# TeensyROM.net
KiCad netlist of a schematic drawn in EAGLE
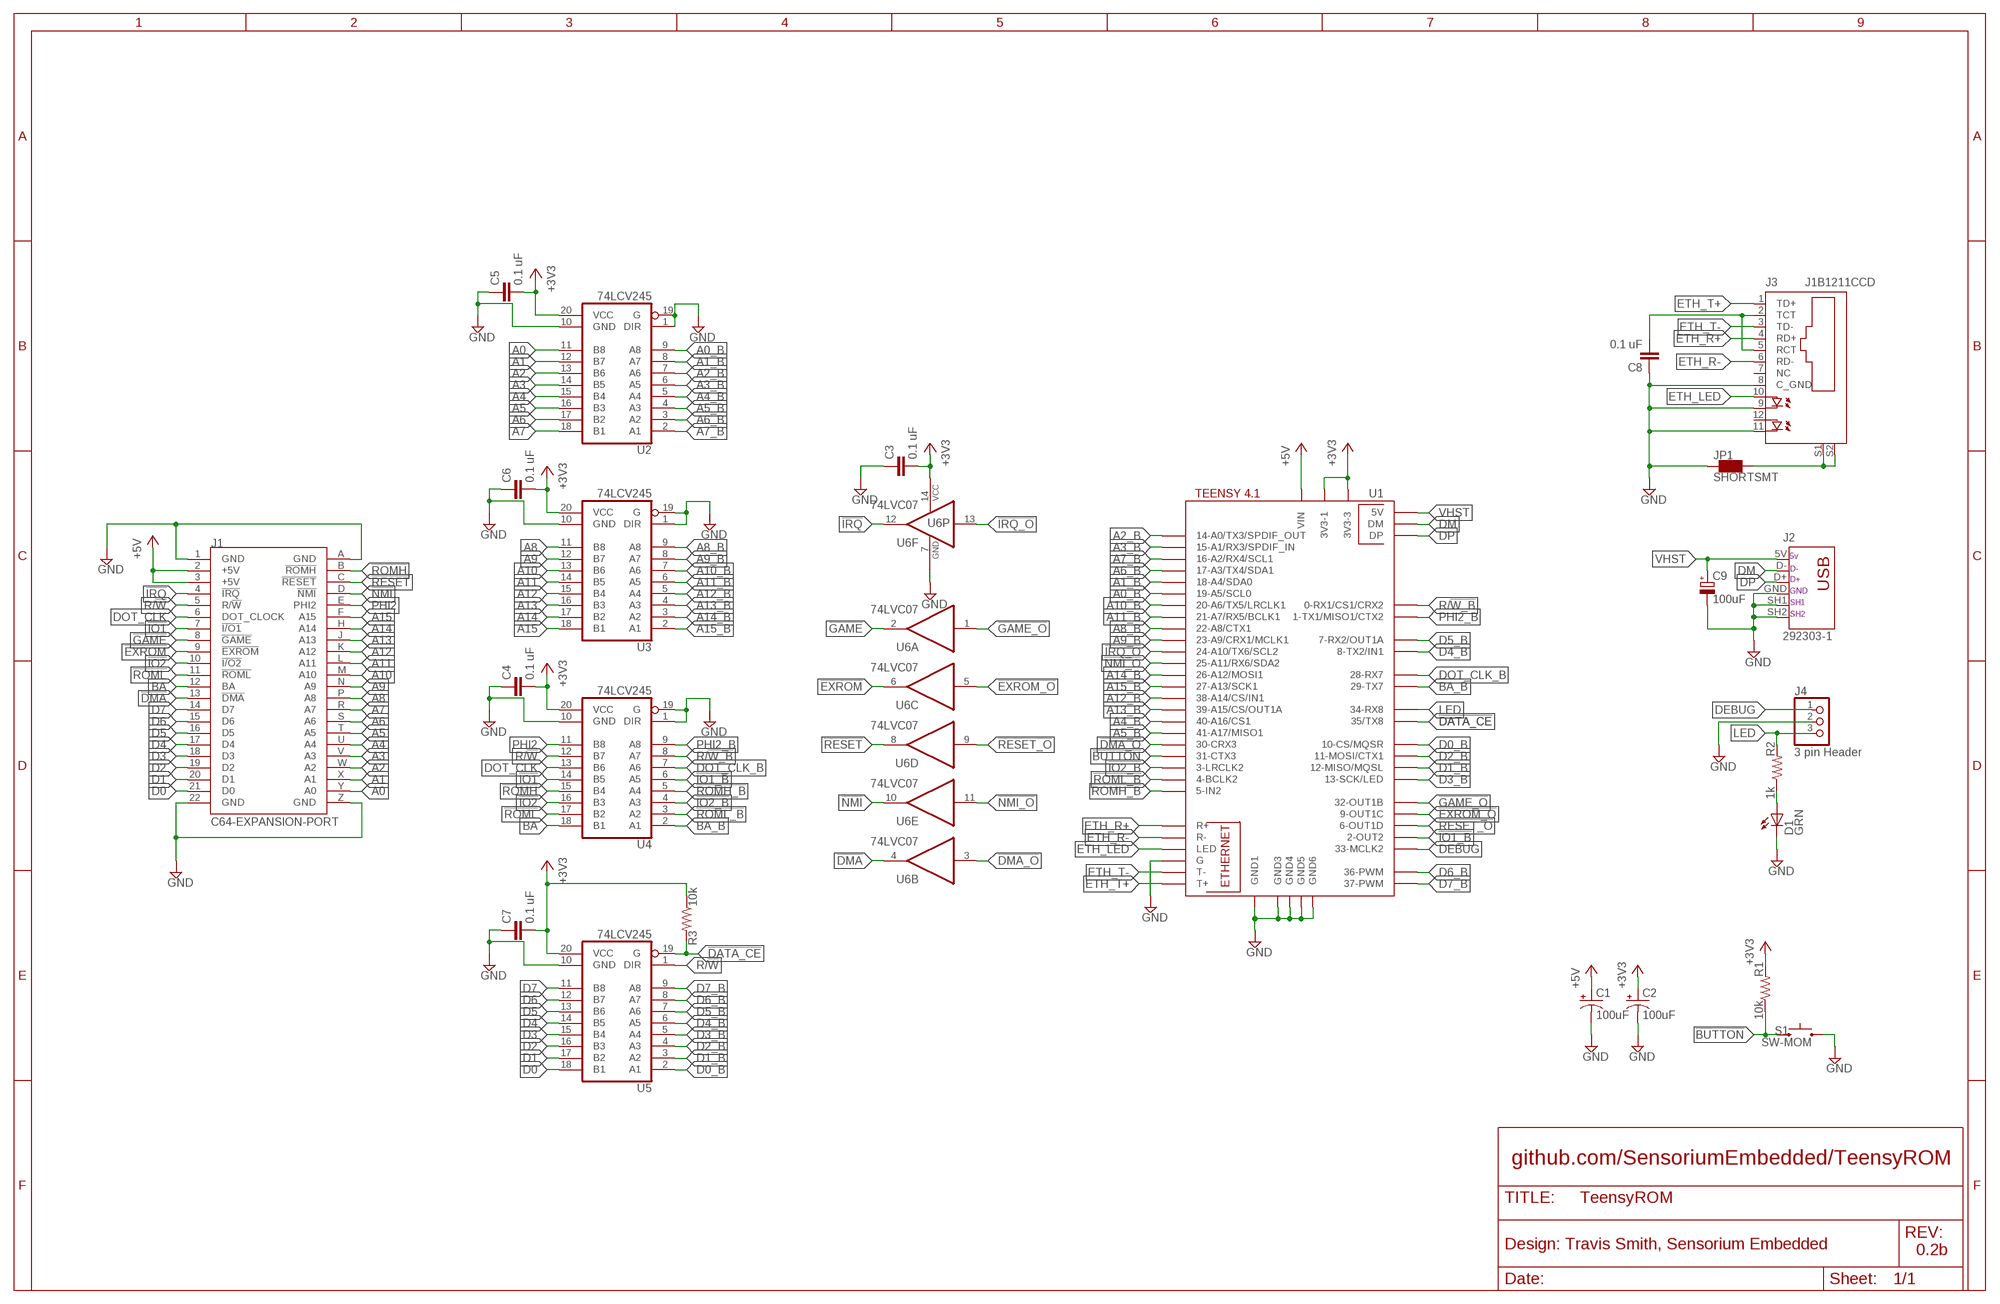
[diagram p0: schematic, sheet 1]

(export (version "E")
  (design (tool "Eeschema 10.0.6"))
  (components
    (comp (ref "C1")
      (value "100uF")
      (footprint "eagle-import:E2,5-6")
      (libsource (lib "eagle-import") (part "CPOL-USE2.5-6"))
    )
    (comp (ref "C2")
      (value "100uF")
      (footprint "eagle-import:E2,5-6")
      (libsource (lib "eagle-import") (part "CPOL-USE2.5-6"))
    )
    (comp (ref "C3")
      (value "0.1 uF")
      (footprint "eagle-import:0805")
      (libsource (lib "eagle-import") (part "CAP-0805-0.1UF-50V"))
    )
    (comp (ref "C4")
      (value "0.1 uF")
      (footprint "eagle-import:0805")
      (libsource (lib "eagle-import") (part "cap_CAP-0805-0.1UF-50V"))
    )
    (comp (ref "C5")
      (value "0.1 uF")
      (footprint "eagle-import:0805")
      (libsource (lib "eagle-import") (part "CAP-0805-0.1UF-50V"))
    )
    (comp (ref "C6")
      (value "0.1 uF")
      (footprint "eagle-import:0805")
      (libsource (lib "eagle-import") (part "cap_CAP-0805-0.1UF-50V"))
    )
    (comp (ref "C7")
      (value "0.1 uF")
      (footprint "eagle-import:0805")
      (libsource (lib "eagle-import") (part "cap_CAP-0805-0.1UF-50V"))
    )
    (comp (ref "C8")
      (value "0.1 uF")
      (footprint "eagle-import:0805")
      (libsource (lib "eagle-import") (part "cap_CAP-0805-0.1UF-50V"))
    )
    (comp (ref "C9")
      (value "100uF")
      (footprint "eagle-import:A_3216-18W")
      (libsource (lib "eagle-import") (part "CPOL-EUA/3216-18W"))
    )
    (comp (ref "D1")
      (value "GRN")
      (footprint "eagle-import:LED-3MM-PTH")
      (libsource (lib "eagle-import") (part "LED-3MM-GRN"))
    )
    (comp (ref "J1")
      (value "C64-EXPANSION-PORT")
      (footprint "eagle-import:EXPANSIO_SQ")
      (libsource (lib "eagle-import") (part "C64-EXPANSIONPNARROW"))
    )
    (comp (ref "J2")
      (value "292303-1")
      (footprint "eagle-import:USB")
      (libsource (lib "eagle-import") (part "USB-787616"))
    )
    (comp (ref "J3")
      (value "J1B1211CCD")
      (footprint "eagle-import:CONN12_J1B1211CCD_WIZ")
      (fields (field (name "COPYRIGHT") "Copyright (C) 2023 Ultra Librarian. All rights reserved."))
      (libsource (lib "eagle-import") (part "J1B1211CCD"))
    )
    (comp (ref "J4")
      (value "3 pin Header")
      (footprint "eagle-import:1X03")
      (libsource (lib "eagle-import") (part "PINHD-1X3"))
    )
    (comp (ref "JP1")
      (value "SHORTSMT")
      (footprint "eagle-import:SHORT")
      (libsource (lib "eagle-import") (part "SHORTSMT"))
    )
    (comp (ref "R1")
      (value "10k")
      (footprint "eagle-import:R0805")
      (libsource (lib "eagle-import") (part "R-US_R0805"))
    )
    (comp (ref "R2")
      (value "1k")
      (footprint "eagle-import:R0805")
      (libsource (lib "eagle-import") (part "R-US_R0805"))
    )
    (comp (ref "R3")
      (value "10k")
      (footprint "eagle-import:R0805")
      (libsource (lib "eagle-import") (part "R-US_R0805"))
    )
    (comp (ref "S1")
      (value "SW-MOM")
      (footprint "eagle-import:TACTILE-PTH")
      (libsource (lib "eagle-import") (part "SWITCH-MOMENTARY-2PTH"))
    )
    (comp (ref "U1")
      (value "TEENSY41")
      (footprint "eagle-import:TEENSY41")
      (libsource (lib "eagle-import") (part "TEENSY41"))
    )
    (comp (ref "U2")
      (value "74LCV245")
      (footprint "eagle-import:SO20W")
      (libsource (lib "eagle-import") (part "74245DWLS"))
    )
    (comp (ref "U3")
      (value "74LCV245")
      (footprint "eagle-import:SO20W")
      (libsource (lib "eagle-import") (part "74245DWLS"))
    )
    (comp (ref "U4")
      (value "74LCV245")
      (footprint "eagle-import:SO20W")
      (libsource (lib "eagle-import") (part "74245DWLS"))
    )
    (comp (ref "U5")
      (value "74LCV245")
      (footprint "eagle-import:SO20W")
      (libsource (lib "eagle-import") (part "74245DWLS"))
    )
    (comp (ref "U6")
      (value "74LVC07")
      (footprint "eagle-import:SO14")
      (libsource (lib "eagle-import") (part "7407DLS"))
    )
  )
  (nets
    (net (code "1") (name "+3V3") (class "Default")
      (node (ref "C2") (pin "+") (pinfunction "+_+") (pintype "passive"))
      (node (ref "C3") (pin "2") (pinfunction "2_2") (pintype "passive"))
      (node (ref "C4") (pin "2") (pinfunction "2_2") (pintype "passive"))
      (node (ref "C5") (pin "2") (pinfunction "2_2") (pintype "passive"))
      (node (ref "C6") (pin "2") (pinfunction "2_2") (pintype "passive"))
      (node (ref "C7") (pin "2") (pinfunction "2_2") (pintype "passive"))
      (node (ref "R1") (pin "2") (pinfunction "2_2") (pintype "passive"))
      (node (ref "R3") (pin "1") (pinfunction "1_1") (pintype "passive"))
      (node (ref "U1") (pin "3V3-1") (pinfunction "3V3-1_3V3-1") (pintype "bidirectional"))
      (node (ref "U1") (pin "3V3-3") (pinfunction "3V3-3_3V3-3") (pintype "bidirectional"))
      (node (ref "U2") (pin "20") (pinfunction "VCC_20") (pintype "bidirectional"))
      (node (ref "U3") (pin "20") (pinfunction "VCC_20") (pintype "bidirectional"))
      (node (ref "U4") (pin "20") (pinfunction "VCC_20") (pintype "bidirectional"))
      (node (ref "U5") (pin "20") (pinfunction "VCC_20") (pintype "bidirectional"))
      (node (ref "U6") (pin "14") (pinfunction "VCC_14") (pintype "bidirectional"))
    )
    (net (code "2") (name "+5V") (class "Default")
      (node (ref "C1") (pin "+") (pinfunction "+_+") (pintype "passive"))
      (node (ref "J1") (pin "2") (pinfunction "+5V_2") (pintype "power_in"))
      (node (ref "J1") (pin "3") (pinfunction "+5V_3") (pintype "power_in"))
      (node (ref "U1") (pin "VIN") (pinfunction "VIN_VIN") (pintype "bidirectional"))
    )
    (net (code "3") (name "/R{slash}~{W_B}") (class "Default")
      (node (ref "U1") (pin "0-RX1/CS1/CRX2") (pinfunction "0-RX1/CS1/CRX2_0-RX1/CS1/CRX2") (pintype "bidirectional"))
      (node (ref "U4") (pin "8") (pinfunction "A7_8") (pintype "bidirectional"))
    )
    (net (code "4") (name "/R{slash}~{W}") (class "Default")
      (node (ref "J1") (pin "5") (pinfunction "R/~{W}_5") (pintype "output"))
      (node (ref "U4") (pin "12") (pinfunction "B7_12") (pintype "bidirectional"))
      (node (ref "U5") (pin "1") (pinfunction "DIR_1") (pintype "input"))
    )
    (net (code "5") (name "/~{BUTTON}") (class "Default")
      (node (ref "R1") (pin "1") (pinfunction "1_1") (pintype "passive"))
      (node (ref "S1") (pin "3") (pinfunction "2_3") (pintype "passive"))
      (node (ref "U1") (pin "31-CTX3") (pinfunction "31-CTX3_31-CTX3") (pintype "bidirectional"))
    )
    (net (code "6") (name "/~{DATA_CE}") (class "Default")
      (node (ref "R3") (pin "2") (pinfunction "2_2") (pintype "passive"))
      (node (ref "U1") (pin "35-TX8") (pinfunction "35/TX8_35-TX8") (pintype "bidirectional"))
      (node (ref "U5") (pin "19") (pinfunction "G_19") (pintype "input"))
    )
    (net (code "7") (name "/~{DMA_O}") (class "Default")
      (node (ref "U1") (pin "30-CRX3") (pinfunction "30-CRX3_30-CRX3") (pintype "bidirectional"))
      (node (ref "U6") (pin "3") (pinfunction "I_3") (pintype "input"))
    )
    (net (code "8") (name "/~{DMA}") (class "Default")
      (node (ref "J1") (pin "13") (pinfunction "~{DMA}_13") (pintype "input"))
      (node (ref "U6") (pin "4") (pinfunction "O_4") (pintype "open_collector"))
    )
    (net (code "9") (name "/~{EXROM_O}") (class "Default")
      (node (ref "U1") (pin "9-OUT1C") (pinfunction "9-OUT1C_9-OUT1C") (pintype "bidirectional"))
      (node (ref "U6") (pin "5") (pinfunction "I_5") (pintype "input"))
    )
    (net (code "10") (name "/~{EXROM}") (class "Default")
      (node (ref "J1") (pin "9") (pinfunction "~{EXROM}_9") (pintype "input"))
      (node (ref "U6") (pin "6") (pinfunction "O_6") (pintype "open_collector"))
    )
    (net (code "11") (name "/~{GAME_O}") (class "Default")
      (node (ref "U1") (pin "32-OUT1B") (pinfunction "32-OUT1B_32-OUT1B") (pintype "bidirectional"))
      (node (ref "U6") (pin "1") (pinfunction "I_1") (pintype "input"))
    )
    (net (code "12") (name "/~{GAME}") (class "Default")
      (node (ref "J1") (pin "8") (pinfunction "~{GAME}_8") (pintype "input"))
      (node (ref "U6") (pin "2") (pinfunction "O_2") (pintype "open_collector"))
    )
    (net (code "13") (name "/~{IO1_B}") (class "Default")
      (node (ref "U1") (pin "2-OUT2") (pinfunction "2-OUT2_2-OUT2") (pintype "bidirectional"))
      (node (ref "U4") (pin "6") (pinfunction "A5_6") (pintype "bidirectional"))
    )
    (net (code "14") (name "/~{IO1}") (class "Default")
      (node (ref "J1") (pin "7") (pinfunction "~{I/O1}_7") (pintype "output"))
      (node (ref "U4") (pin "14") (pinfunction "B5_14") (pintype "bidirectional"))
    )
    (net (code "15") (name "/~{IO2_B}") (class "Default")
      (node (ref "U1") (pin "3-LRCLK2") (pinfunction "3-LRCLK2_3-LRCLK2") (pintype "bidirectional"))
      (node (ref "U4") (pin "4") (pinfunction "A3_4") (pintype "bidirectional"))
    )
    (net (code "16") (name "/~{IO2}") (class "Default")
      (node (ref "J1") (pin "10") (pinfunction "~{I/O2}_10") (pintype "output"))
      (node (ref "U4") (pin "16") (pinfunction "B3_16") (pintype "bidirectional"))
    )
    (net (code "17") (name "/~{IRQ_O}") (class "Default")
      (node (ref "U1") (pin "24-A10/TX6/SCL2") (pinfunction "24-A10/TX6/SCL2_24-A10/TX6/SCL2") (pintype "bidirectional"))
      (node (ref "U6") (pin "13") (pinfunction "I_13") (pintype "input"))
    )
    (net (code "18") (name "/~{IRQ}") (class "Default")
      (node (ref "J1") (pin "4") (pinfunction "~{IRQ}_4") (pintype "input"))
      (node (ref "U6") (pin "12") (pinfunction "O_12") (pintype "open_collector"))
    )
    (net (code "19") (name "/~{NMI_O}") (class "Default")
      (node (ref "U1") (pin "25-A11/RX6/SDA2") (pinfunction "25-A11/RX6/SDA2_25-A11/RX6/SDA2") (pintype "bidirectional"))
      (node (ref "U6") (pin "11") (pinfunction "I_11") (pintype "input"))
    )
    (net (code "20") (name "/~{NMI}") (class "Default")
      (node (ref "J1") (pin "D") (pinfunction "~{NMI}_D") (pintype "input"))
      (node (ref "U6") (pin "10") (pinfunction "O_10") (pintype "open_collector"))
    )
    (net (code "21") (name "/~{RESET_O}") (class "Default")
      (node (ref "U1") (pin "6-OUT1D") (pinfunction "6-OUT1D_6-OUT1D") (pintype "bidirectional"))
      (node (ref "U6") (pin "9") (pinfunction "I_9") (pintype "input"))
    )
    (net (code "22") (name "/~{RESET}") (class "Default")
      (node (ref "J1") (pin "C") (pinfunction "~{RESET}_C") (pintype "open_collector"))
      (node (ref "U6") (pin "8") (pinfunction "O_8") (pintype "open_collector"))
    )
    (net (code "23") (name "/~{ROMH_B}") (class "Default")
      (node (ref "U1") (pin "5-IN2") (pinfunction "5-IN2_5-IN2") (pintype "bidirectional"))
      (node (ref "U4") (pin "5") (pinfunction "A4_5") (pintype "bidirectional"))
    )
    (net (code "24") (name "/~{ROMH}") (class "Default")
      (node (ref "J1") (pin "B") (pinfunction "~{ROMH}_B") (pintype "output"))
      (node (ref "U4") (pin "15") (pinfunction "B4_15") (pintype "bidirectional"))
    )
    (net (code "25") (name "/~{ROML_B}") (class "Default")
      (node (ref "U1") (pin "4-BCLK2") (pinfunction "4-BCLK2_4-BCLK2") (pintype "bidirectional"))
      (node (ref "U4") (pin "3") (pinfunction "A2_3") (pintype "bidirectional"))
    )
    (net (code "26") (name "/~{ROML}") (class "Default")
      (node (ref "J1") (pin "11") (pinfunction "~{ROML}_11") (pintype "output"))
      (node (ref "U4") (pin "17") (pinfunction "B2_17") (pintype "bidirectional"))
    )
    (net (code "27") (name "A0") (class "Default")
      (node (ref "J1") (pin "Y") (pinfunction "A0_Y") (pintype "bidirectional"))
      (node (ref "U2") (pin "11") (pinfunction "B8_11") (pintype "bidirectional"))
    )
    (net (code "28") (name "A0_B") (class "Default")
      (node (ref "U1") (pin "19-A5/SCL0") (pinfunction "19-A5/SCL0_19-A5/SCL0") (pintype "bidirectional"))
      (node (ref "U2") (pin "9") (pinfunction "A8_9") (pintype "bidirectional"))
    )
    (net (code "29") (name "A1") (class "Default")
      (node (ref "J1") (pin "X") (pinfunction "A1_X") (pintype "bidirectional"))
      (node (ref "U2") (pin "12") (pinfunction "B7_12") (pintype "bidirectional"))
    )
    (net (code "30") (name "A1_B") (class "Default")
      (node (ref "U1") (pin "18-A4/SDA0") (pinfunction "18-A4/SDA0_18-A4/SDA0") (pintype "bidirectional"))
      (node (ref "U2") (pin "8") (pinfunction "A7_8") (pintype "bidirectional"))
    )
    (net (code "31") (name "A2") (class "Default")
      (node (ref "J1") (pin "W") (pinfunction "A2_W") (pintype "bidirectional"))
      (node (ref "U2") (pin "13") (pinfunction "B6_13") (pintype "bidirectional"))
    )
    (net (code "32") (name "A2_B") (class "Default")
      (node (ref "U1") (pin "14-A0/TX3/SPDIF_OUT") (pinfunction "14-A0/TX3/SPDIF_OUT_14-A0/TX3/SPDIF_OUT") (pintype "bidirectional"))
      (node (ref "U2") (pin "7") (pinfunction "A6_7") (pintype "bidirectional"))
    )
    (net (code "33") (name "A3") (class "Default")
      (node (ref "J1") (pin "V") (pinfunction "A3_V") (pintype "bidirectional"))
      (node (ref "U2") (pin "14") (pinfunction "B5_14") (pintype "bidirectional"))
    )
    (net (code "34") (name "A3_B") (class "Default")
      (node (ref "U1") (pin "15-A1/RX3/SPDIF_IN") (pinfunction "15-A1/RX3/SPDIF_IN_15-A1/RX3/SPDIF_IN") (pintype "bidirectional"))
      (node (ref "U2") (pin "6") (pinfunction "A5_6") (pintype "bidirectional"))
    )
    (net (code "35") (name "A4") (class "Default")
      (node (ref "J1") (pin "U") (pinfunction "A4_U") (pintype "bidirectional"))
      (node (ref "U2") (pin "15") (pinfunction "B4_15") (pintype "bidirectional"))
    )
    (net (code "36") (name "A4_B") (class "Default")
      (node (ref "U1") (pin "40-A16/CS1") (pinfunction "40-A16/CS1_40-A16/CS1") (pintype "bidirectional"))
      (node (ref "U2") (pin "5") (pinfunction "A4_5") (pintype "bidirectional"))
    )
    (net (code "37") (name "A5") (class "Default")
      (node (ref "J1") (pin "T") (pinfunction "A5_T") (pintype "bidirectional"))
      (node (ref "U2") (pin "16") (pinfunction "B3_16") (pintype "bidirectional"))
    )
    (net (code "38") (name "A5_B") (class "Default")
      (node (ref "U1") (pin "41-A17/MISO1") (pinfunction "41-A17/MISO1_41-A17/MISO1") (pintype "bidirectional"))
      (node (ref "U2") (pin "4") (pinfunction "A3_4") (pintype "bidirectional"))
    )
    (net (code "39") (name "A6") (class "Default")
      (node (ref "J1") (pin "S") (pinfunction "A6_S") (pintype "bidirectional"))
      (node (ref "U2") (pin "17") (pinfunction "B2_17") (pintype "bidirectional"))
    )
    (net (code "40") (name "A6_B") (class "Default")
      (node (ref "U1") (pin "17-A3/TX4/SDA1") (pinfunction "17-A3/TX4/SDA1_17-A3/TX4/SDA1") (pintype "bidirectional"))
      (node (ref "U2") (pin "3") (pinfunction "A2_3") (pintype "bidirectional"))
    )
    (net (code "41") (name "A7") (class "Default")
      (node (ref "J1") (pin "R") (pinfunction "A7_R") (pintype "bidirectional"))
      (node (ref "U2") (pin "18") (pinfunction "B1_18") (pintype "bidirectional"))
    )
    (net (code "42") (name "A7_B") (class "Default")
      (node (ref "U1") (pin "16-A2/RX4/SCL1") (pinfunction "16-A2/RX4/SCL1_16-A2/RX4/SCL1") (pintype "bidirectional"))
      (node (ref "U2") (pin "2") (pinfunction "A1_2") (pintype "bidirectional"))
    )
    (net (code "43") (name "A8") (class "Default")
      (node (ref "J1") (pin "P") (pinfunction "A8_P") (pintype "bidirectional"))
      (node (ref "U3") (pin "11") (pinfunction "B8_11") (pintype "bidirectional"))
    )
    (net (code "44") (name "A8_B") (class "Default")
      (node (ref "U1") (pin "22-A8/CTX1") (pinfunction "22-A8/CTX1_22-A8/CTX1") (pintype "bidirectional"))
      (node (ref "U3") (pin "9") (pinfunction "A8_9") (pintype "bidirectional"))
    )
    (net (code "45") (name "A9") (class "Default")
      (node (ref "J1") (pin "N") (pinfunction "A9_N") (pintype "bidirectional"))
      (node (ref "U3") (pin "12") (pinfunction "B7_12") (pintype "bidirectional"))
    )
    (net (code "46") (name "A9_B") (class "Default")
      (node (ref "U1") (pin "23-A9/CRX1/MCLK1") (pinfunction "23-A9/CRX1/MCLK1_23-A9/CRX1/MCLK1") (pintype "bidirectional"))
      (node (ref "U3") (pin "8") (pinfunction "A7_8") (pintype "bidirectional"))
    )
    (net (code "47") (name "A10") (class "Default")
      (node (ref "J1") (pin "M") (pinfunction "A10_M") (pintype "bidirectional"))
      (node (ref "U3") (pin "13") (pinfunction "B6_13") (pintype "bidirectional"))
    )
    (net (code "48") (name "A10_B") (class "Default")
      (node (ref "U1") (pin "20-A6/TX5/LRCLK1") (pinfunction "20-A6/TX5/LRCLK1_20-A6/TX5/LRCLK1") (pintype "bidirectional"))
      (node (ref "U3") (pin "7") (pinfunction "A6_7") (pintype "bidirectional"))
    )
    (net (code "49") (name "A11") (class "Default")
      (node (ref "J1") (pin "L") (pinfunction "A11_L") (pintype "bidirectional"))
      (node (ref "U3") (pin "14") (pinfunction "B5_14") (pintype "bidirectional"))
    )
    (net (code "50") (name "A11_B") (class "Default")
      (node (ref "U1") (pin "21-A7/RX5/BCLK1") (pinfunction "21-A7/RX5/BCLK1_21-A7/RX5/BCLK1") (pintype "bidirectional"))
      (node (ref "U3") (pin "6") (pinfunction "A5_6") (pintype "bidirectional"))
    )
    (net (code "51") (name "A12") (class "Default")
      (node (ref "J1") (pin "K") (pinfunction "A12_K") (pintype "bidirectional"))
      (node (ref "U3") (pin "15") (pinfunction "B4_15") (pintype "bidirectional"))
    )
    (net (code "52") (name "A12_B") (class "Default")
      (node (ref "U1") (pin "38-A14/CS/IN1") (pinfunction "38-A14/CS/IN1_38-A14/CS/IN1") (pintype "bidirectional"))
      (node (ref "U3") (pin "5") (pinfunction "A4_5") (pintype "bidirectional"))
    )
    (net (code "53") (name "A13") (class "Default")
      (node (ref "J1") (pin "J") (pinfunction "A13_J") (pintype "bidirectional"))
      (node (ref "U3") (pin "16") (pinfunction "B3_16") (pintype "bidirectional"))
    )
    (net (code "54") (name "A13_B") (class "Default")
      (node (ref "U1") (pin "39-A15/CS/OUT1A") (pinfunction "39-A15/CS/OUT1A_39-A15/CS/OUT1A") (pintype "bidirectional"))
      (node (ref "U3") (pin "4") (pinfunction "A3_4") (pintype "bidirectional"))
    )
    (net (code "55") (name "A14") (class "Default")
      (node (ref "J1") (pin "H") (pinfunction "A14_H") (pintype "bidirectional"))
      (node (ref "U3") (pin "17") (pinfunction "B2_17") (pintype "bidirectional"))
    )
    (net (code "56") (name "A14_B") (class "Default")
      (node (ref "U1") (pin "26-A12/MOSI1") (pinfunction "26-A12/MOSI1_26-A12/MOSI1") (pintype "bidirectional"))
      (node (ref "U3") (pin "3") (pinfunction "A2_3") (pintype "bidirectional"))
    )
    (net (code "57") (name "A15") (class "Default")
      (node (ref "J1") (pin "F") (pinfunction "A15_F") (pintype "bidirectional"))
      (node (ref "U3") (pin "18") (pinfunction "B1_18") (pintype "bidirectional"))
    )
    (net (code "58") (name "A15_B") (class "Default")
      (node (ref "U1") (pin "27-A13/SCK1") (pinfunction "27-A13/SCK1_27-A13/SCK1") (pintype "bidirectional"))
      (node (ref "U3") (pin "2") (pinfunction "A1_2") (pintype "bidirectional"))
    )
    (net (code "59") (name "BA") (class "Default")
      (node (ref "J1") (pin "12") (pinfunction "BA_12") (pintype "output"))
      (node (ref "U4") (pin "18") (pinfunction "B1_18") (pintype "bidirectional"))
    )
    (net (code "60") (name "BA_B") (class "Default")
      (node (ref "U1") (pin "29-TX7") (pinfunction "29-TX7_29-TX7") (pintype "bidirectional"))
      (node (ref "U4") (pin "2") (pinfunction "A1_2") (pintype "bidirectional"))
    )
    (net (code "61") (name "D0") (class "Default")
      (node (ref "J1") (pin "21") (pinfunction "D0_21") (pintype "bidirectional"))
      (node (ref "U5") (pin "18") (pinfunction "B1_18") (pintype "bidirectional"))
    )
    (net (code "62") (name "D0_B") (class "Default")
      (node (ref "U1") (pin "10-CS\\MQSR") (pinfunction "10-CS/MQSR_10-CS\\MQSR") (pintype "bidirectional"))
      (node (ref "U5") (pin "2") (pinfunction "A1_2") (pintype "bidirectional"))
    )
    (net (code "63") (name "D1") (class "Default")
      (node (ref "J1") (pin "20") (pinfunction "D1_20") (pintype "bidirectional"))
      (node (ref "U5") (pin "17") (pinfunction "B2_17") (pintype "bidirectional"))
    )
    (net (code "64") (name "D1_B") (class "Default")
      (node (ref "U1") (pin "12-MISO/MQSL") (pinfunction "12-MISO/MQSL_12-MISO/MQSL") (pintype "bidirectional"))
      (node (ref "U5") (pin "3") (pinfunction "A2_3") (pintype "bidirectional"))
    )
    (net (code "65") (name "D2") (class "Default")
      (node (ref "J1") (pin "19") (pinfunction "D2_19") (pintype "bidirectional"))
      (node (ref "U5") (pin "16") (pinfunction "B3_16") (pintype "bidirectional"))
    )
    (net (code "66") (name "D2_B") (class "Default")
      (node (ref "U1") (pin "11-MOSI/CTX1") (pinfunction "11-MOSI/CTX1_11-MOSI/CTX1") (pintype "bidirectional"))
      (node (ref "U5") (pin "4") (pinfunction "A3_4") (pintype "bidirectional"))
    )
    (net (code "67") (name "D3") (class "Default")
      (node (ref "J1") (pin "18") (pinfunction "D3_18") (pintype "bidirectional"))
      (node (ref "U5") (pin "15") (pinfunction "B4_15") (pintype "bidirectional"))
    )
    (net (code "68") (name "D3_B") (class "Default")
      (node (ref "U1") (pin "13-SCK/LED") (pinfunction "13-SCK/LED_13-SCK/LED") (pintype "bidirectional"))
      (node (ref "U5") (pin "5") (pinfunction "A4_5") (pintype "bidirectional"))
    )
    (net (code "69") (name "D4") (class "Default")
      (node (ref "J1") (pin "17") (pinfunction "D4_17") (pintype "bidirectional"))
      (node (ref "U5") (pin "14") (pinfunction "B5_14") (pintype "bidirectional"))
    )
    (net (code "70") (name "D4_B") (class "Default")
      (node (ref "U1") (pin "8-TX2/IN1") (pinfunction "8-TX2/IN1_8-TX2/IN1") (pintype "bidirectional"))
      (node (ref "U5") (pin "6") (pinfunction "A5_6") (pintype "bidirectional"))
    )
    (net (code "71") (name "D5") (class "Default")
      (node (ref "J1") (pin "16") (pinfunction "D5_16") (pintype "bidirectional"))
      (node (ref "U5") (pin "13") (pinfunction "B6_13") (pintype "bidirectional"))
    )
    (net (code "72") (name "D5_B") (class "Default")
      (node (ref "U1") (pin "7-RX2/OUT1A") (pinfunction "7-RX2/OUT1A_7-RX2/OUT1A") (pintype "bidirectional"))
      (node (ref "U5") (pin "7") (pinfunction "A6_7") (pintype "bidirectional"))
    )
    (net (code "73") (name "D6") (class "Default")
      (node (ref "J1") (pin "15") (pinfunction "D6_15") (pintype "bidirectional"))
      (node (ref "U5") (pin "12") (pinfunction "B7_12") (pintype "bidirectional"))
    )
    (net (code "74") (name "D6_B") (class "Default")
      (node (ref "U1") (pin "36-PWM") (pinfunction "36-PWM_36-PWM") (pintype "bidirectional"))
      (node (ref "U5") (pin "8") (pinfunction "A7_8") (pintype "bidirectional"))
    )
    (net (code "75") (name "D7") (class "Default")
      (node (ref "J1") (pin "14") (pinfunction "D7_14") (pintype "bidirectional"))
      (node (ref "U5") (pin "11") (pinfunction "B8_11") (pintype "bidirectional"))
    )
    (net (code "76") (name "D7_B") (class "Default")
      (node (ref "U1") (pin "37-PWM") (pinfunction "37-PWM_37-PWM") (pintype "bidirectional"))
      (node (ref "U5") (pin "9") (pinfunction "A8_9") (pintype "bidirectional"))
    )
    (net (code "77") (name "DEBUG") (class "Default")
      (node (ref "J4") (pin "1") (pinfunction "1_1") (pintype "passive"))
      (node (ref "U1") (pin "33-MCLK2") (pinfunction "33-MCLK2_33-MCLK2") (pintype "bidirectional"))
    )
    (net (code "78") (name "DM") (class "Default")
      (node (ref "J2") (pin "D-") (pinfunction "2_D-") (pintype "passive"))
      (node (ref "U1") (pin "DM") (pinfunction "DM_DM") (pintype "bidirectional"))
    )
    (net (code "79") (name "DOT_CLK") (class "Default")
      (node (ref "J1") (pin "6") (pinfunction "DOT_CLOCK_6") (pintype "output"))
      (node (ref "U4") (pin "13") (pinfunction "B6_13") (pintype "bidirectional"))
    )
    (net (code "80") (name "DOT_CLK_B") (class "Default")
      (node (ref "U1") (pin "28-RX7") (pinfunction "28-RX7_28-RX7") (pintype "bidirectional"))
      (node (ref "U4") (pin "7") (pinfunction "A6_7") (pintype "bidirectional"))
    )
    (net (code "81") (name "DP") (class "Default")
      (node (ref "J2") (pin "D+") (pinfunction "3_D+") (pintype "passive"))
      (node (ref "U1") (pin "DP") (pinfunction "DP_DP") (pintype "bidirectional"))
    )
    (net (code "82") (name "ETH_LED") (class "Default")
      (node (ref "J3") (pin "10") (pinfunction "A_10") (pintype "passive"))
      (node (ref "U1") (pin "LED") (pinfunction "LED_LED") (pintype "bidirectional"))
    )
    (net (code "83") (name "ETH_R+") (class "Default")
      (node (ref "J3") (pin "4") (pinfunction "RD+_4") (pintype "passive"))
      (node (ref "U1") (pin "R+") (pinfunction "R+_R+") (pintype "bidirectional"))
    )
    (net (code "84") (name "ETH_R-") (class "Default")
      (node (ref "J3") (pin "6") (pinfunction "RD-_6") (pintype "passive"))
      (node (ref "U1") (pin "R-") (pinfunction "R-_R-") (pintype "bidirectional"))
    )
    (net (code "85") (name "ETH_T+") (class "Default")
      (node (ref "J3") (pin "1") (pinfunction "TD+_1") (pintype "passive"))
      (node (ref "U1") (pin "T+") (pinfunction "T+_T+") (pintype "bidirectional"))
    )
    (net (code "86") (name "ETH_T-") (class "Default")
      (node (ref "J3") (pin "3") (pinfunction "TD-_3") (pintype "passive"))
      (node (ref "U1") (pin "T-") (pinfunction "T-_T-") (pintype "bidirectional"))
    )
    (net (code "87") (name "GND") (class "Default")
      (node (ref "C1") (pin "-") (pinfunction "-_-") (pintype "passive"))
      (node (ref "C2") (pin "-") (pinfunction "-_-") (pintype "passive"))
      (node (ref "C3") (pin "1") (pinfunction "1_1") (pintype "passive"))
      (node (ref "C4") (pin "1") (pinfunction "1_1") (pintype "passive"))
      (node (ref "C5") (pin "1") (pinfunction "1_1") (pintype "passive"))
      (node (ref "C6") (pin "1") (pinfunction "1_1") (pintype "passive"))
      (node (ref "C7") (pin "1") (pinfunction "1_1") (pintype "passive"))
      (node (ref "C8") (pin "1") (pinfunction "1_1") (pintype "passive"))
      (node (ref "C9") (pin "-") (pinfunction "-_-") (pintype "passive"))
      (node (ref "D1") (pin "K") (pinfunction "C_K") (pintype "passive"))
      (node (ref "J1") (pin "1") (pinfunction "GND_1") (pintype "power_in"))
      (node (ref "J1") (pin "22") (pinfunction "GND_22") (pintype "power_in"))
      (node (ref "J1") (pin "A") (pinfunction "GND_A") (pintype "power_in"))
      (node (ref "J1") (pin "Z") (pinfunction "GND_Z") (pintype "power_in"))
      (node (ref "J2") (pin "GND") (pinfunction "4_GND") (pintype "passive"))
      (node (ref "J2") (pin "SH1") (pinfunction "5_SH1") (pintype "passive"))
      (node (ref "J2") (pin "SH2") (pinfunction "6_SH2") (pintype "passive"))
      (node (ref "J3") (pin "11") (pinfunction "C1_11") (pintype "passive"))
      (node (ref "J3") (pin "8") (pinfunction "C_GND_8") (pintype "passive"))
      (node (ref "J3") (pin "9") (pinfunction "C_9") (pintype "passive"))
      (node (ref "J4") (pin "2") (pinfunction "2_2") (pintype "passive"))
      (node (ref "JP1") (pin "1") (pinfunction "1_1") (pintype "passive"))
      (node (ref "S1") (pin "1") (pinfunction "1_1") (pintype "passive"))
      (node (ref "U1") (pin "G") (pinfunction "G_G") (pintype "bidirectional"))
      (node (ref "U1") (pin "GND1") (pinfunction "GND1_GND1") (pintype "bidirectional"))
      (node (ref "U1") (pin "GND3") (pinfunction "GND3_GND3") (pintype "bidirectional"))
      (node (ref "U1") (pin "GND4") (pinfunction "GND4_GND4") (pintype "bidirectional"))
      (node (ref "U1") (pin "GND5") (pinfunction "GND5_GND5") (pintype "bidirectional"))
      (node (ref "U1") (pin "GND6") (pinfunction "GND6_GND6") (pintype "bidirectional"))
      (node (ref "U2") (pin "1") (pinfunction "DIR_1") (pintype "input"))
      (node (ref "U2") (pin "10") (pinfunction "GND_10") (pintype "bidirectional"))
      (node (ref "U2") (pin "19") (pinfunction "G_19") (pintype "input"))
      (node (ref "U3") (pin "1") (pinfunction "DIR_1") (pintype "input"))
      (node (ref "U3") (pin "10") (pinfunction "GND_10") (pintype "bidirectional"))
      (node (ref "U3") (pin "19") (pinfunction "G_19") (pintype "input"))
      (node (ref "U4") (pin "1") (pinfunction "DIR_1") (pintype "input"))
      (node (ref "U4") (pin "10") (pinfunction "GND_10") (pintype "bidirectional"))
      (node (ref "U4") (pin "19") (pinfunction "G_19") (pintype "input"))
      (node (ref "U5") (pin "10") (pinfunction "GND_10") (pintype "bidirectional"))
      (node (ref "U6") (pin "7") (pinfunction "GND_7") (pintype "power_in"))
    )
    (net (code "88") (name "LED") (class "Default")
      (node (ref "J4") (pin "3") (pinfunction "3_3") (pintype "passive"))
      (node (ref "R2") (pin "2") (pinfunction "2_2") (pintype "passive"))
      (node (ref "U1") (pin "34-RX8") (pinfunction "34-RX8_34-RX8") (pintype "bidirectional"))
    )
    (net (code "89") (name "Net-(D1-PadA)") (class "Default")
      (node (ref "D1") (pin "A") (pinfunction "A_A") (pintype "passive"))
      (node (ref "R2") (pin "1") (pinfunction "1_1") (pintype "passive"))
    )
    (net (code "90") (name "Net-(J3-PadS1)") (class "Default")
      (node (ref "J3") (pin "S1") (pinfunction "S1_S1") (pintype "passive"))
      (node (ref "J3") (pin "S2") (pinfunction "S2_S2") (pintype "passive"))
      (node (ref "JP1") (pin "2") (pinfunction "2_2") (pintype "passive"))
    )
    (net (code "91") (name "Net-(J3-RCT)") (class "Default")
      (node (ref "C8") (pin "2") (pinfunction "2_2") (pintype "passive"))
      (node (ref "J3") (pin "2") (pinfunction "TCT_2") (pintype "passive"))
      (node (ref "J3") (pin "5") (pinfunction "RCT_5") (pintype "passive"))
    )
    (net (code "92") (name "PHI2") (class "Default")
      (node (ref "J1") (pin "E") (pinfunction "PHI2_E") (pintype "output"))
      (node (ref "U4") (pin "11") (pinfunction "B8_11") (pintype "bidirectional"))
    )
    (net (code "93") (name "PHI2_B") (class "Default")
      (node (ref "U1") (pin "1-TX1/MISO1/CTX2") (pinfunction "1-TX1/MISO1/CTX2_1-TX1/MISO1/CTX2") (pintype "bidirectional"))
      (node (ref "U4") (pin "9") (pinfunction "A8_9") (pintype "bidirectional"))
    )
    (net (code "94") (name "VHST") (class "Default")
      (node (ref "C9") (pin "+") (pinfunction "+_+") (pintype "passive"))
      (node (ref "J2") (pin "5V") (pinfunction "1_5V") (pintype "passive"))
      (node (ref "U1") (pin "+5V") (pinfunction "5V_+5V") (pintype "bidirectional"))
    )
    (net (code "95") (name "unconnected-(J3-A1-Pad12)") (class "Default")
      (node (ref "J3") (pin "12") (pinfunction "A1_12") (pintype "passive"))
    )
    (net (code "96") (name "unconnected-(J3-NC-Pad7)") (class "Default")
      (node (ref "J3") (pin "7") (pinfunction "NC_7") (pintype "passive"))
    )
  )
)
